# TinyMicroGameboy.net
KiCad netlist of a schematic drawn in EAGLE
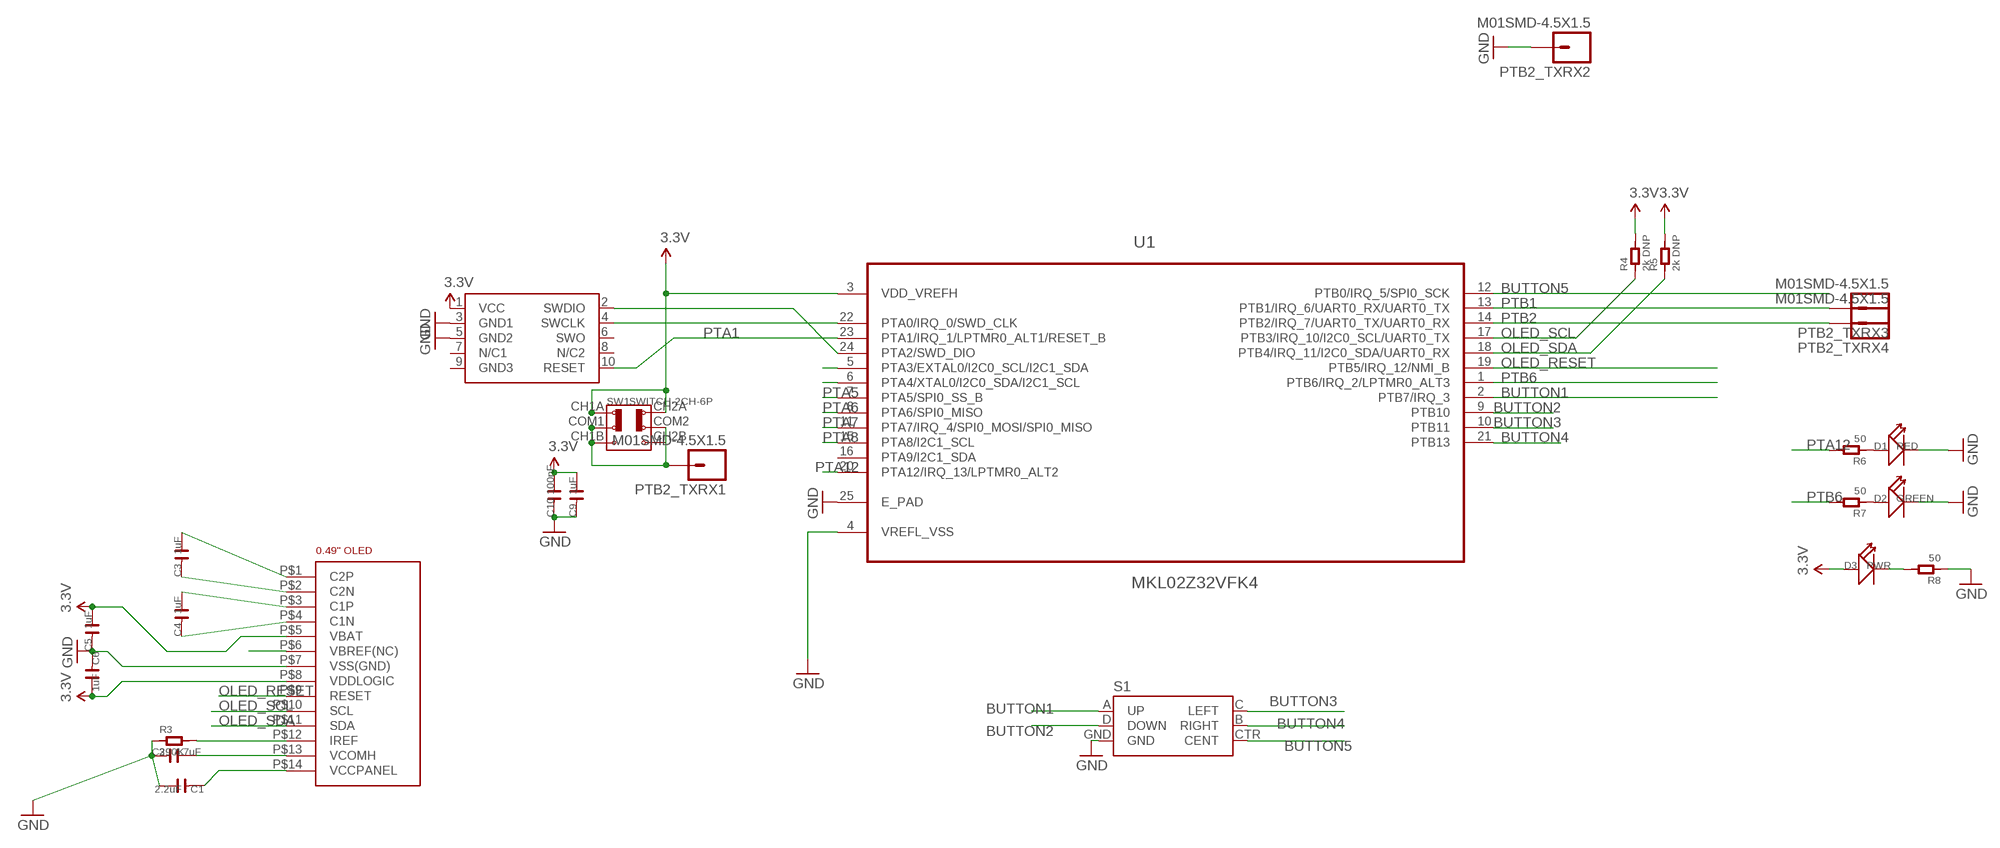
[diagram p0: schematic, sheet 1]

(export (version "E")
  (design (tool "Eeschema 10.0.6"))
  (components
    (comp (ref "C1")
      (value "2.2uF")
      (footprint "eagle-import:C0603")
      (libsource (lib "eagle-import") (part "C-0603"))
    )
    (comp (ref "C2")
      (value "4.7uF")
      (footprint "eagle-import:C0603")
      (libsource (lib "eagle-import") (part "C-0603"))
    )
    (comp (ref "C3")
      (value "1uF")
      (footprint "eagle-import:C0603")
      (libsource (lib "eagle-import") (part "C-0603"))
    )
    (comp (ref "C4")
      (value "1uF")
      (footprint "eagle-import:C0603")
      (libsource (lib "eagle-import") (part "C-0603"))
    )
    (comp (ref "C5")
      (value "1uF")
      (footprint "eagle-import:C0603")
      (libsource (lib "eagle-import") (part "C-0603"))
    )
    (comp (ref "C6")
      (value "1uF")
      (footprint "eagle-import:C0603")
      (libsource (lib "eagle-import") (part "C-0603"))
    )
    (comp (ref "C9")
      (value "1uF")
      (footprint "eagle-import:C0603")
      (libsource (lib "eagle-import") (part "C-0603"))
    )
    (comp (ref "C10")
      (value "100nF")
      (footprint "eagle-import:C0603")
      (libsource (lib "eagle-import") (part "C-0603"))
    )
    (comp (ref "D1")
      (value "RED")
      (footprint "eagle-import:LED0603")
      (libsource (lib "eagle-import") (part "LED"))
    )
    (comp (ref "D2")
      (value "GREEN")
      (footprint "eagle-import:LED0603")
      (libsource (lib "eagle-import") (part "LED"))
    )
    (comp (ref "D3")
      (value "PWR")
      (footprint "eagle-import:LED0603")
      (libsource (lib "eagle-import") (part "LED"))
    )
    (comp (ref "PTB2_TXRX1")
      (value "M01SMD-4.5X1.5")
      (footprint "eagle-import:PAD-1.5X4.5")
      (libsource (lib "eagle-import") (part "M01SMD-4.5X1.5"))
    )
    (comp (ref "PTB2_TXRX2")
      (value "M01SMD-4.5X1.5")
      (footprint "eagle-import:PAD-1.5X4.5")
      (libsource (lib "eagle-import") (part "M01SMD-4.5X1.5"))
    )
    (comp (ref "PTB2_TXRX3")
      (value "M01SMD-4.5X1.5")
      (footprint "eagle-import:PAD-1.5X4.5")
      (libsource (lib "eagle-import") (part "M01SMD-4.5X1.5"))
    )
    (comp (ref "PTB2_TXRX4")
      (value "M01SMD-4.5X1.5")
      (footprint "eagle-import:PAD-1.5X4.5")
      (libsource (lib "eagle-import") (part "M01SMD-4.5X1.5"))
    )
    (comp (ref "R3")
      (value "390K")
      (footprint "eagle-import:R0603")
      (libsource (lib "eagle-import") (part "R-0603"))
    )
    (comp (ref "R4")
      (value "2k DNP")
      (footprint "eagle-import:R0603")
      (libsource (lib "eagle-import") (part "R-0603"))
    )
    (comp (ref "R5")
      (value "2k DNP")
      (footprint "eagle-import:R0603")
      (libsource (lib "eagle-import") (part "R-0603"))
    )
    (comp (ref "R6")
      (value "50")
      (footprint "eagle-import:R0603")
      (libsource (lib "eagle-import") (part "R-0603"))
    )
    (comp (ref "R7")
      (value "50")
      (footprint "eagle-import:R0603")
      (libsource (lib "eagle-import") (part "R-0603"))
    )
    (comp (ref "R8")
      (value "50")
      (footprint "eagle-import:R0603")
      (libsource (lib "eagle-import") (part "R-0603"))
    )
    (comp (ref "S1")
      (value "JOYSTICK_MINI")
      (footprint "eagle-import:JOYSTICK_MINI")
      (libsource (lib "eagle-import") (part "JOYSTICK_MINI"))
    )
    (comp (ref "SW1")
      (value "SWITCH-2CH-6P")
      (footprint "eagle-import:6P-2CH-SIDEMOUNT")
      (libsource (lib "eagle-import") (part "SWITCH-2CH-6P"))
    )
    (comp (ref "SWD1")
      (value "CORTEX_SWD")
      (footprint "eagle-import:M50-3600542")
      (libsource (lib "eagle-import") (part "CORTEX_SWD"))
    )
    (comp (ref "U$1")
      (value "0.49\"OLEDFOLDED")
      (footprint "eagle-import:0.49_-FPC-0.7-14-FOLDED")
      (libsource (lib "eagle-import") (part "0.49{dblquote}OLEDFOLDED"))
    )
    (comp (ref "U1")
      (value "MKL02Z32VFK4")
      (footprint "eagle-import:QFN50P400X400X100-25N")
      (libsource (lib "eagle-import") (part "MKL02Z32VFK4"))
    )
  )
  (nets
    (net (code "1") (name "/BUTTON1") (class "Default")
      (node (ref "S1") (pin "A") (pinfunction "UP_A") (pintype "bidirectional"))
      (node (ref "U1") (pin "2") (pinfunction "PTB7/IRQ_3_2") (pintype "bidirectional"))
    )
    (net (code "2") (name "/BUTTON2") (class "Default")
      (node (ref "S1") (pin "D") (pinfunction "DOWN_D") (pintype "bidirectional"))
      (node (ref "U1") (pin "9") (pinfunction "PTB10_9") (pintype "bidirectional"))
    )
    (net (code "3") (name "/BUTTON3") (class "Default")
      (node (ref "S1") (pin "C") (pinfunction "LEFT_C") (pintype "bidirectional"))
      (node (ref "U1") (pin "10") (pinfunction "PTB11_10") (pintype "bidirectional"))
    )
    (net (code "4") (name "/BUTTON4") (class "Default")
      (node (ref "S1") (pin "B") (pinfunction "RIGHT_B") (pintype "bidirectional"))
      (node (ref "U1") (pin "21") (pinfunction "PTB13_21") (pintype "bidirectional"))
    )
    (net (code "5") (name "/BUTTON5") (class "Default")
      (node (ref "S1") (pin "CTR") (pinfunction "CENT_CTR") (pintype "bidirectional"))
      (node (ref "U1") (pin "12") (pinfunction "PTB0/IRQ_5/SPI0_SCK_12") (pintype "bidirectional"))
    )
    (net (code "6") (name "/OLED_RESET") (class "Default")
      (node (ref "U$1") (pin "P$9") (pinfunction "RESET_P$9") (pintype "bidirectional"))
      (node (ref "U1") (pin "19") (pinfunction "PTB5/IRQ_12/NMI_B_19") (pintype "bidirectional"))
    )
    (net (code "7") (name "/OLED_SCL") (class "Default")
      (node (ref "R4") (pin "1") (pinfunction "1_1") (pintype "bidirectional"))
      (node (ref "U$1") (pin "P$10") (pinfunction "SCL_P$10") (pintype "bidirectional"))
      (node (ref "U1") (pin "17") (pinfunction "PTB3/IRQ_10/I2C0_SCL/UART0_TX_17") (pintype "bidirectional"))
    )
    (net (code "8") (name "/OLED_SDA") (class "Default")
      (node (ref "R5") (pin "1") (pinfunction "1_1") (pintype "bidirectional"))
      (node (ref "U$1") (pin "P$11") (pinfunction "SDA_P$11") (pintype "bidirectional"))
      (node (ref "U1") (pin "18") (pinfunction "PTB4/IRQ_11/I2C0_SDA/UART0_RX_18") (pintype "bidirectional"))
    )
    (net (code "9") (name "/PTA1") (class "Default")
      (node (ref "SWD1") (pin "10") (pinfunction "RESET_10") (pintype "bidirectional"))
      (node (ref "U1") (pin "23") (pinfunction "PTA1/IRQ_1/LPTMR0_ALT1/RESET_B_23") (pintype "bidirectional"))
    )
    (net (code "10") (name "/PTA5") (class "Default")
      (node (ref "U1") (pin "7") (pinfunction "PTA5/SPI0_SS_B_7") (pintype "bidirectional"))
    )
    (net (code "11") (name "/PTA6") (class "Default")
      (node (ref "U1") (pin "8") (pinfunction "PTA6/SPI0_MISO_8") (pintype "bidirectional"))
    )
    (net (code "12") (name "/PTA7") (class "Default")
      (node (ref "U1") (pin "11") (pinfunction "PTA7/IRQ_4/SPI0_MOSI/SPI0_MISO_11") (pintype "bidirectional"))
    )
    (net (code "13") (name "/PTA8") (class "Default")
      (node (ref "U1") (pin "15") (pinfunction "PTA8/I2C1_SCL_15") (pintype "bidirectional"))
    )
    (net (code "14") (name "/PTA12") (class "Default")
      (node (ref "R6") (pin "2") (pinfunction "2_2") (pintype "bidirectional"))
      (node (ref "U1") (pin "20") (pinfunction "PTA12/IRQ_13/LPTMR0_ALT2_20") (pintype "bidirectional"))
    )
    (net (code "15") (name "/PTB1") (class "Default")
      (node (ref "PTB2_TXRX3") (pin "P$1") (pinfunction "1_P$1") (pintype "passive"))
      (node (ref "U1") (pin "13") (pinfunction "PTB1/IRQ_6/UART0_RX/UART0_TX_13") (pintype "bidirectional"))
    )
    (net (code "16") (name "/PTB2") (class "Default")
      (node (ref "PTB2_TXRX4") (pin "P$1") (pinfunction "1_P$1") (pintype "passive"))
      (node (ref "U1") (pin "14") (pinfunction "PTB2/IRQ_7/UART0_TX/UART0_RX_14") (pintype "bidirectional"))
    )
    (net (code "17") (name "/PTB6") (class "Default")
      (node (ref "R7") (pin "2") (pinfunction "2_2") (pintype "bidirectional"))
      (node (ref "U1") (pin "1") (pinfunction "PTB6/IRQ_2/LPTMR0_ALT3_1") (pintype "bidirectional"))
    )
    (net (code "18") (name "3.3V") (class "Default")
      (node (ref "C10") (pin "2") (pinfunction "2_2") (pintype "bidirectional"))
      (node (ref "C5") (pin "2") (pinfunction "2_2") (pintype "bidirectional"))
      (node (ref "C6") (pin "2") (pinfunction "2_2") (pintype "bidirectional"))
      (node (ref "C9") (pin "2") (pinfunction "2_2") (pintype "bidirectional"))
      (node (ref "D3") (pin "+") (pinfunction "+_+") (pintype "passive"))
      (node (ref "R4") (pin "2") (pinfunction "2_2") (pintype "bidirectional"))
      (node (ref "R5") (pin "2") (pinfunction "2_2") (pintype "bidirectional"))
      (node (ref "SW1") (pin "CH1A") (pinfunction "CH1A_CH1A") (pintype "bidirectional"))
      (node (ref "SW1") (pin "CH2A") (pinfunction "CH2A_CH2A") (pintype "bidirectional"))
      (node (ref "SWD1") (pin "1") (pinfunction "VCC_1") (pintype "bidirectional"))
      (node (ref "U$1") (pin "P$5") (pinfunction "VBAT_P$5") (pintype "bidirectional"))
      (node (ref "U$1") (pin "P$8") (pinfunction "VDDLOGIC_P$8") (pintype "bidirectional"))
      (node (ref "U1") (pin "3") (pinfunction "VDD_VREFH_3") (pintype "power_in"))
    )
    (net (code "19") (name "GND") (class "Default")
      (node (ref "C1") (pin "2") (pinfunction "2_2") (pintype "bidirectional"))
      (node (ref "C10") (pin "1") (pinfunction "1_1") (pintype "bidirectional"))
      (node (ref "C2") (pin "1") (pinfunction "1_1") (pintype "bidirectional"))
      (node (ref "C5") (pin "1") (pinfunction "1_1") (pintype "bidirectional"))
      (node (ref "C6") (pin "1") (pinfunction "1_1") (pintype "bidirectional"))
      (node (ref "C9") (pin "1") (pinfunction "1_1") (pintype "bidirectional"))
      (node (ref "D1") (pin "-") (pinfunction "-_-") (pintype "passive"))
      (node (ref "D2") (pin "-") (pinfunction "-_-") (pintype "passive"))
      (node (ref "PTB2_TXRX2") (pin "P$1") (pinfunction "1_P$1") (pintype "passive"))
      (node (ref "R3") (pin "1") (pinfunction "1_1") (pintype "bidirectional"))
      (node (ref "R8") (pin "1") (pinfunction "1_1") (pintype "bidirectional"))
      (node (ref "S1") (pin "GND") (pinfunction "GND_GND") (pintype "bidirectional"))
      (node (ref "SWD1") (pin "3") (pinfunction "GND1_3") (pintype "bidirectional"))
      (node (ref "SWD1") (pin "5") (pinfunction "GND2_5") (pintype "bidirectional"))
      (node (ref "U$1") (pin "P$7") (pinfunction "VSS(GND)_P$7") (pintype "bidirectional"))
      (node (ref "U1") (pin "25") (pinfunction "E_PAD_25") (pintype "passive"))
      (node (ref "U1") (pin "4") (pinfunction "VREFL_VSS_4") (pintype "passive"))
    )
    (net (code "20") (name "Net-(D1-Pad+)") (class "Default")
      (node (ref "D1") (pin "+") (pinfunction "+_+") (pintype "passive"))
      (node (ref "R6") (pin "1") (pinfunction "1_1") (pintype "bidirectional"))
    )
    (net (code "21") (name "Net-(D2-Pad+)") (class "Default")
      (node (ref "D2") (pin "+") (pinfunction "+_+") (pintype "passive"))
      (node (ref "R7") (pin "1") (pinfunction "1_1") (pintype "bidirectional"))
    )
    (net (code "22") (name "Net-(D3-Pad-)") (class "Default")
      (node (ref "D3") (pin "-") (pinfunction "-_-") (pintype "passive"))
      (node (ref "R8") (pin "2") (pinfunction "2_2") (pintype "bidirectional"))
    )
    (net (code "23") (name "Net-(PTB2_TXRX1-1)") (class "Default")
      (node (ref "PTB2_TXRX1") (pin "P$1") (pinfunction "1_P$1") (pintype "passive"))
      (node (ref "SW1") (pin "CH1B") (pinfunction "CH1B_CH1B") (pintype "bidirectional"))
      (node (ref "SW1") (pin "CH2B") (pinfunction "CH2B_CH2B") (pintype "bidirectional"))
      (node (ref "SW1") (pin "COM1") (pinfunction "COM1_COM1") (pintype "bidirectional"))
      (node (ref "SW1") (pin "COM2") (pinfunction "COM2_COM2") (pintype "bidirectional"))
    )
    (net (code "24") (name "Net-(SWD1-SWCLK)") (class "Default")
      (node (ref "SWD1") (pin "4") (pinfunction "SWCLK_4") (pintype "bidirectional"))
      (node (ref "U1") (pin "22") (pinfunction "PTA0/IRQ_0/SWD_CLK_22") (pintype "bidirectional"))
    )
    (net (code "25") (name "Net-(SWD1-SWDIO)") (class "Default")
      (node (ref "SWD1") (pin "2") (pinfunction "SWDIO_2") (pintype "bidirectional"))
      (node (ref "U1") (pin "24") (pinfunction "PTA2/SWD_DIO_24") (pintype "bidirectional"))
    )
    (net (code "26") (name "Net-(U$1-C1N)") (class "Default")
      (node (ref "C4") (pin "1") (pinfunction "1_1") (pintype "bidirectional"))
      (node (ref "U$1") (pin "P$4") (pinfunction "C1N_P$4") (pintype "bidirectional"))
    )
    (net (code "27") (name "Net-(U$1-C1P)") (class "Default")
      (node (ref "C4") (pin "2") (pinfunction "2_2") (pintype "bidirectional"))
      (node (ref "U$1") (pin "P$3") (pinfunction "C1P_P$3") (pintype "bidirectional"))
    )
    (net (code "28") (name "Net-(U$1-C2N)") (class "Default")
      (node (ref "C3") (pin "1") (pinfunction "1_1") (pintype "bidirectional"))
      (node (ref "U$1") (pin "P$2") (pinfunction "C2N_P$2") (pintype "bidirectional"))
    )
    (net (code "29") (name "Net-(U$1-C2P)") (class "Default")
      (node (ref "C3") (pin "2") (pinfunction "2_2") (pintype "bidirectional"))
      (node (ref "U$1") (pin "P$1") (pinfunction "C2P_P$1") (pintype "bidirectional"))
    )
    (net (code "30") (name "Net-(U$1-IREF)") (class "Default")
      (node (ref "R3") (pin "2") (pinfunction "2_2") (pintype "bidirectional"))
      (node (ref "U$1") (pin "P$12") (pinfunction "IREF_P$12") (pintype "bidirectional"))
    )
    (net (code "31") (name "Net-(U$1-VCCPANEL)") (class "Default")
      (node (ref "C1") (pin "1") (pinfunction "1_1") (pintype "bidirectional"))
      (node (ref "U$1") (pin "P$14") (pinfunction "VCCPANEL_P$14") (pintype "bidirectional"))
    )
    (net (code "32") (name "Net-(U$1-VCOMH)") (class "Default")
      (node (ref "C2") (pin "2") (pinfunction "2_2") (pintype "bidirectional"))
      (node (ref "U$1") (pin "P$13") (pinfunction "VCOMH_P$13") (pintype "bidirectional"))
    )
    (net (code "33") (name "unconnected-(SWD1-GND3-Pad9)") (class "Default")
      (node (ref "SWD1") (pin "9") (pinfunction "GND3_9") (pintype "bidirectional"))
    )
    (net (code "34") (name "unconnected-(SWD1-N{slash}C1-Pad7)") (class "Default")
      (node (ref "SWD1") (pin "7") (pinfunction "N/C1_7") (pintype "bidirectional"))
    )
    (net (code "35") (name "unconnected-(SWD1-N{slash}C2-Pad8)") (class "Default")
      (node (ref "SWD1") (pin "8") (pinfunction "N/C2_8") (pintype "bidirectional"))
    )
    (net (code "36") (name "unconnected-(SWD1-SWO-Pad6)") (class "Default")
      (node (ref "SWD1") (pin "6") (pinfunction "SWO_6") (pintype "bidirectional"))
    )
    (net (code "37") (name "unconnected-(U$1-VBREF(NC)-PadP$6)") (class "Default")
      (node (ref "U$1") (pin "P$6") (pinfunction "VBREF(NC)_P$6") (pintype "bidirectional"))
    )
    (net (code "38") (name "unconnected-(U1-PTA3{slash}EXTAL0{slash}I2C0_SCL{slash}I2C1_SDA-Pad5)") (class "Default")
      (node (ref "U1") (pin "5") (pinfunction "PTA3/EXTAL0/I2C0_SCL/I2C1_SDA_5") (pintype "bidirectional"))
    )
    (net (code "39") (name "unconnected-(U1-PTA4{slash}XTAL0{slash}I2C0_SDA{slash}I2C1_SCL-Pad6)") (class "Default")
      (node (ref "U1") (pin "6") (pinfunction "PTA4/XTAL0/I2C0_SDA/I2C1_SCL_6") (pintype "bidirectional"))
    )
    (net (code "40") (name "unconnected-(U1-PTA9{slash}I2C1_SDA-Pad16)") (class "Default")
      (node (ref "U1") (pin "16") (pinfunction "PTA9/I2C1_SDA_16") (pintype "bidirectional"))
    )
  )
)
